# FPGA_DDR3_IO.net
KiCad netlist of a schematic drawn in Altium Designer
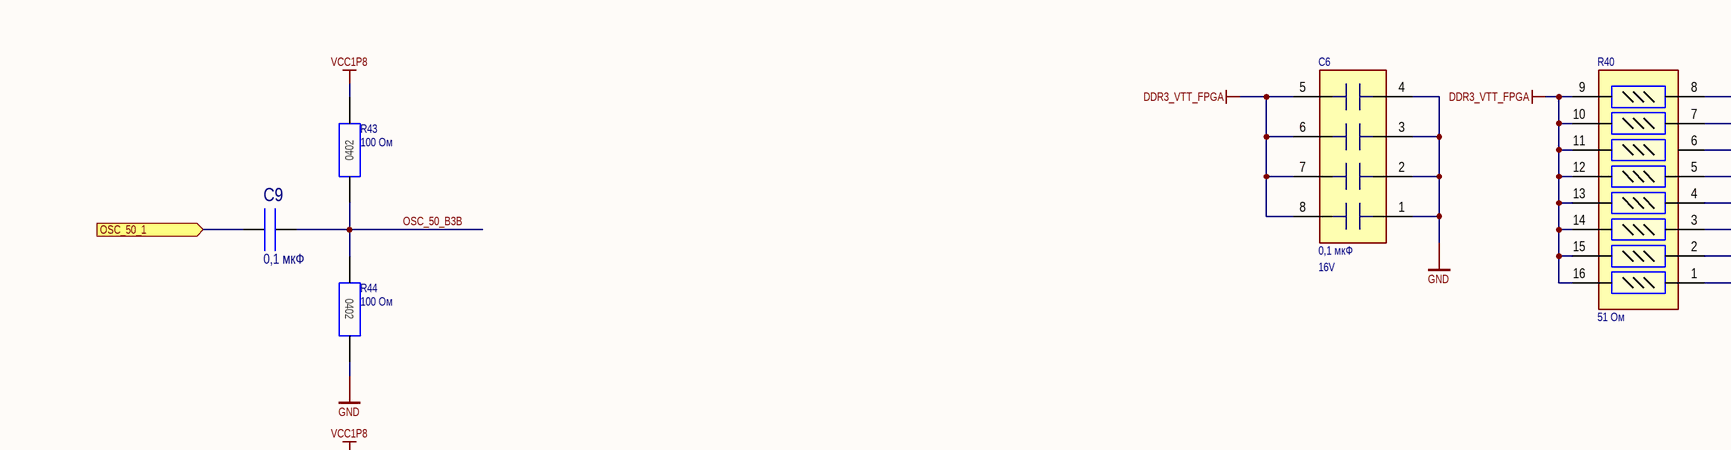
[diagram p0: FPGA_DDR3&IO.SchDoc, top left]
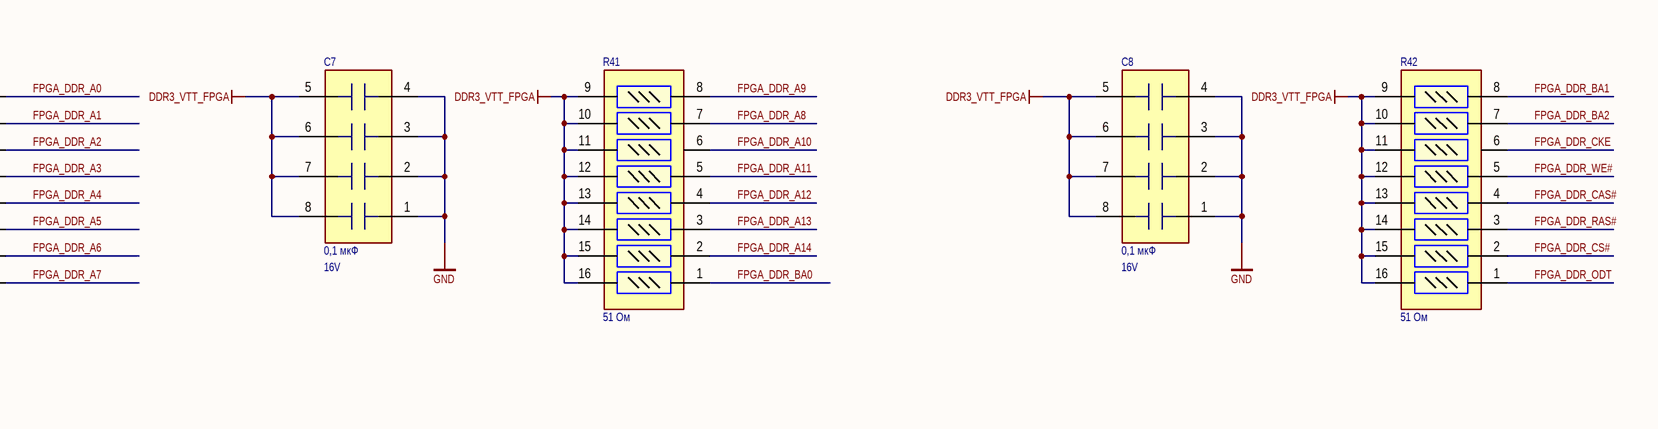
[diagram p1: FPGA_DDR3&IO.SchDoc, top right]
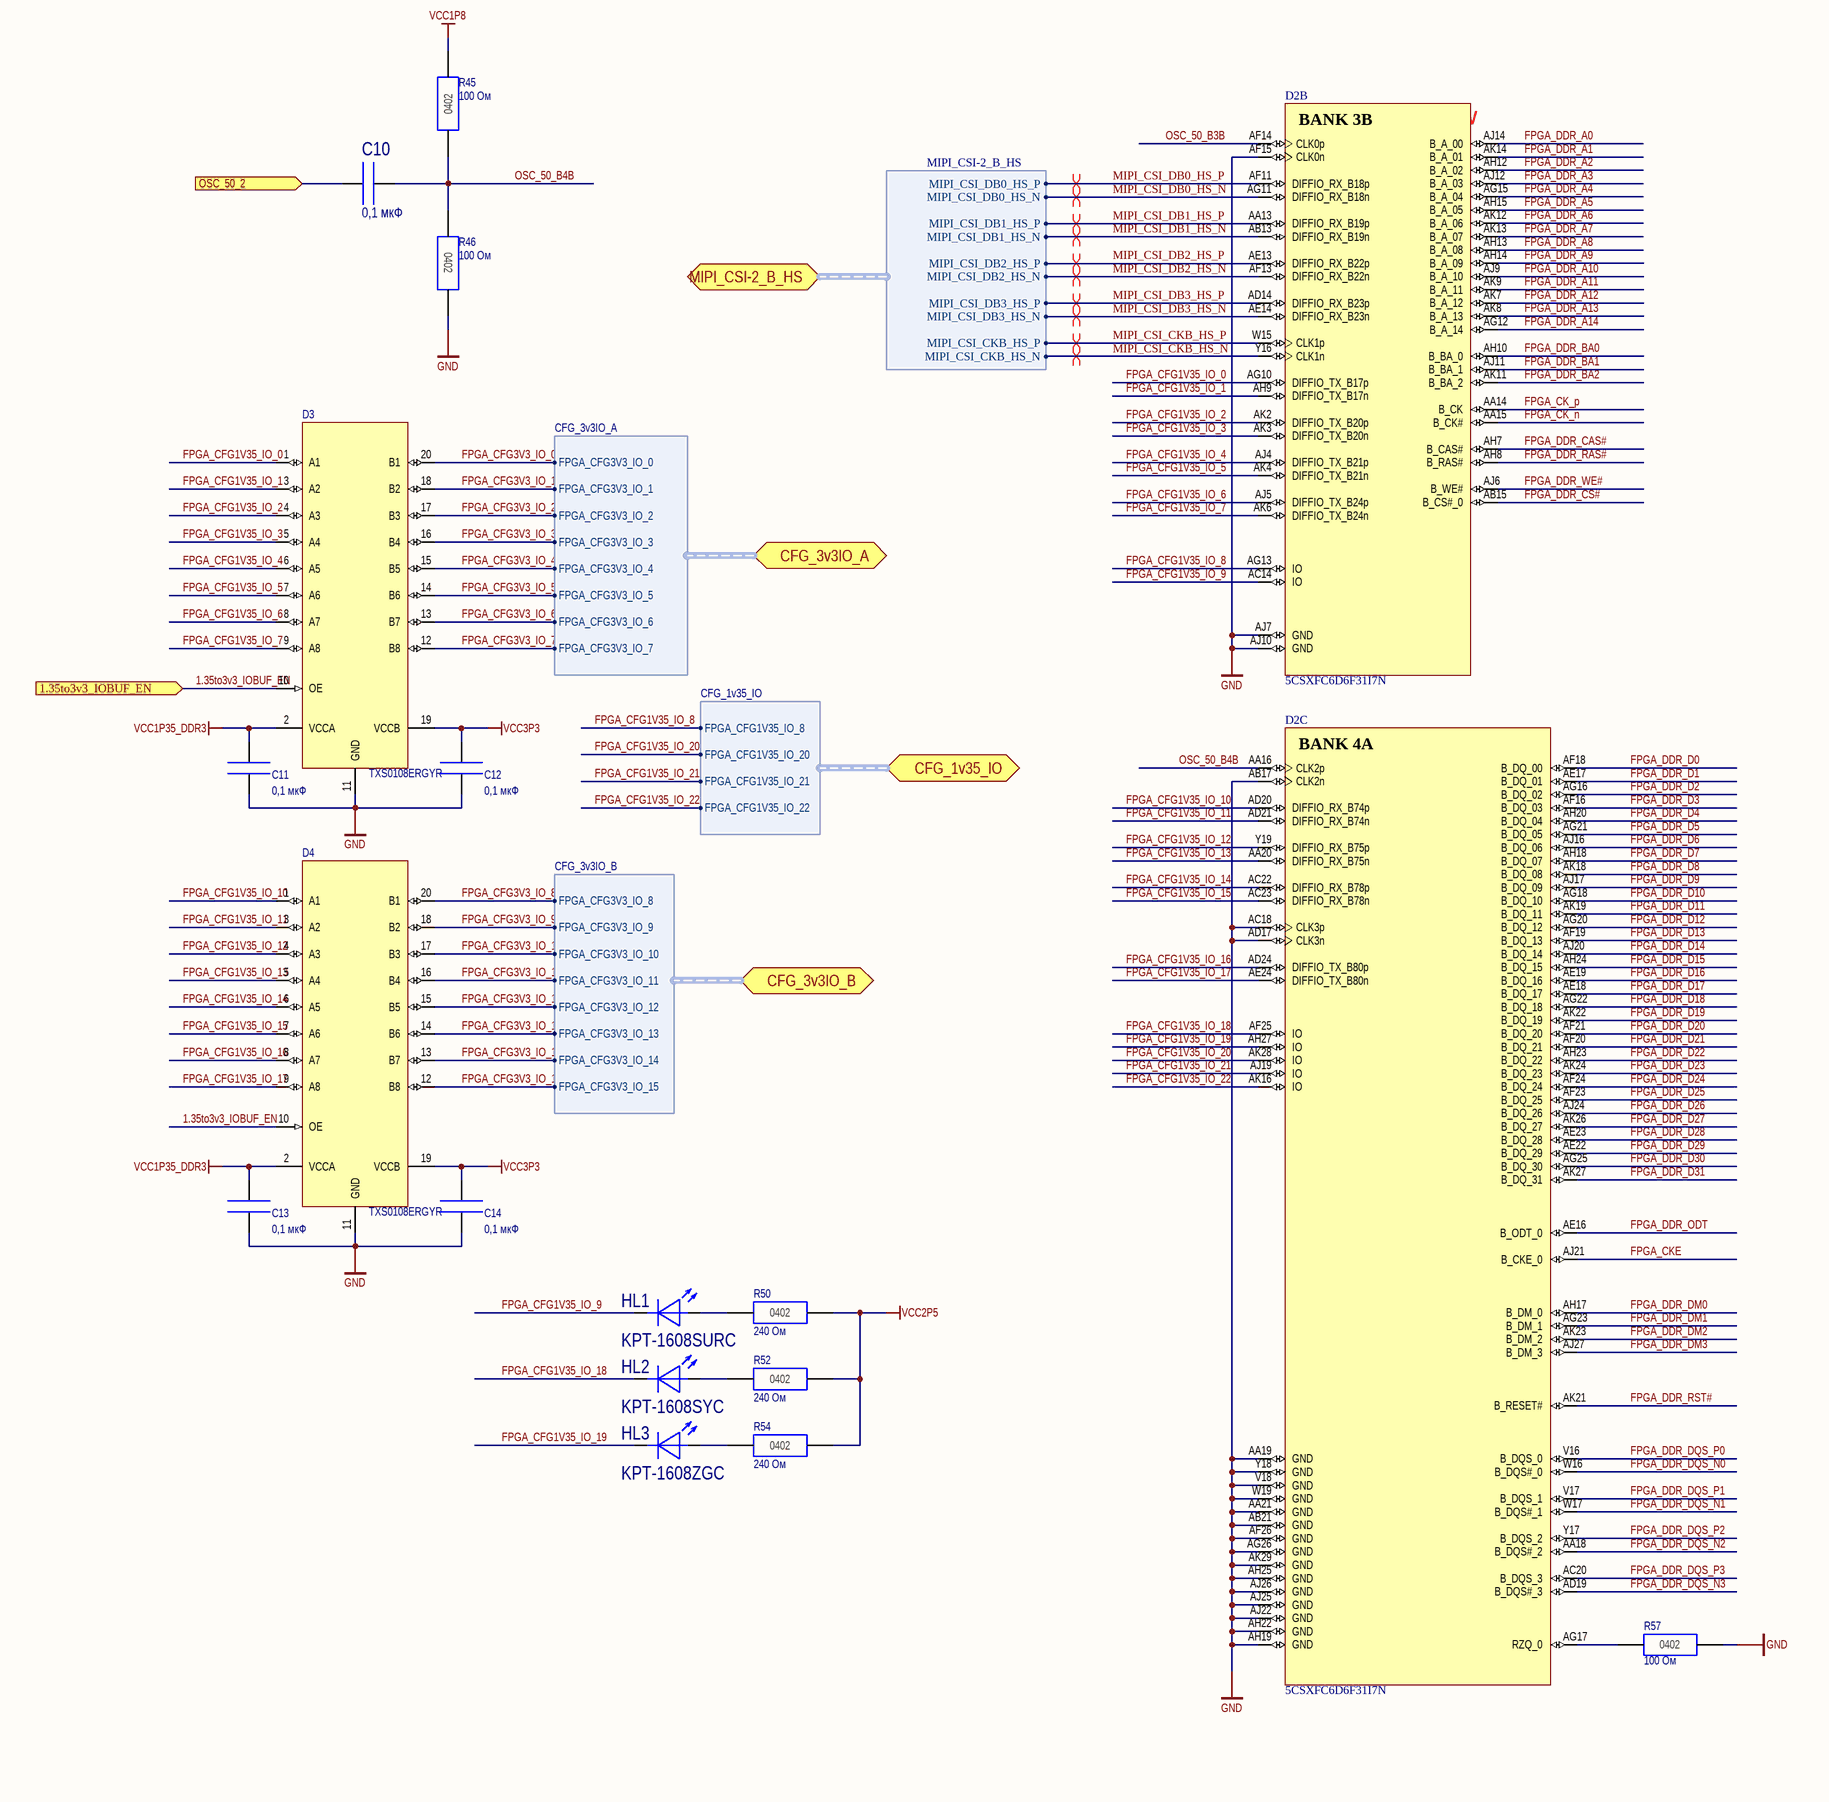
[diagram p2: FPGA_DDR3&IO.SchDoc, bottom left]
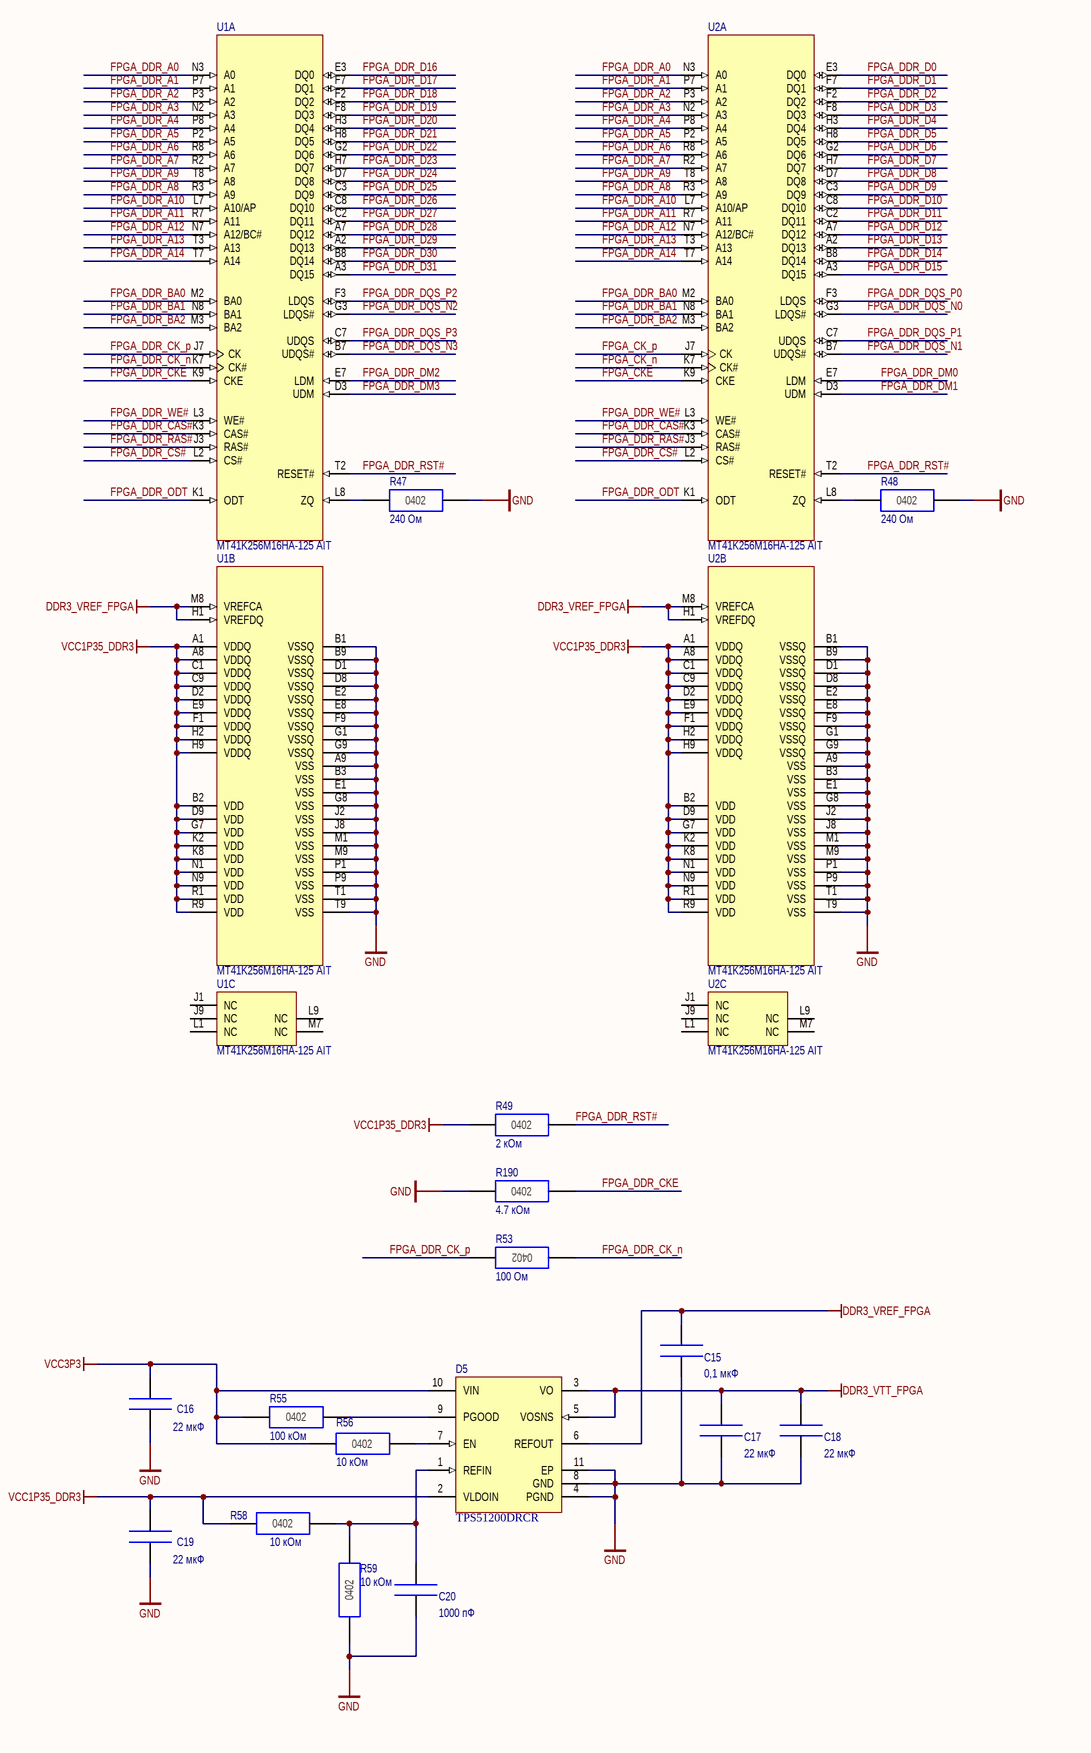
[diagram p3: FPGA_DDR3&IO.SchDoc, bottom right]

(export (version "E")
  (design (tool "Eeschema 10.0.6"))
  (components
    (comp (ref "C6")
      (value "0,1 мкФ")
      (footprint "CAF-80P319X159-8N")
      (description "Чип конденсатор керамический")
      (fields (field (name "V") "16V") (field (name "Comment") "W3A4YC104KAT2A"))
      (libsource (lib "SD_IC") (part "W3A4YC104KAT2A"))
    )
    (comp (ref "C7")
      (value "0,1 мкФ")
      (footprint "CAF-80P319X159-8N")
      (description "Чип конденсатор керамический")
      (fields (field (name "V") "16V") (field (name "Comment") "W3A4YC104KAT2A"))
      (libsource (lib "SD_IC") (part "W3A4YC104KAT2A"))
    )
    (comp (ref "C8")
      (value "0,1 мкФ")
      (footprint "CAF-80P319X159-8N")
      (description "Чип конденсатор керамический")
      (fields (field (name "V") "16V") (field (name "Comment") "W3A4YC104KAT2A"))
      (libsource (lib "SD_IC") (part "W3A4YC104KAT2A"))
    )
    (comp (ref "C9")
      (value "0,1 мкФ")
      (footprint "CC0402(1005)")
      (description "Чип конденсатор керамический")
      (fields (field (name "Comment") "CC0402-X7R-0,1 мкФ-20%-10В"))
      (libsource (lib "Чип конденсаторы") (part "CC0402-X7R-#-20%-10В"))
    )
    (comp (ref "C10")
      (value "0,1 мкФ")
      (footprint "CC0402(1005)")
      (description "Чип конденсатор керамический")
      (fields (field (name "Comment") "CC0402-X7R-0,1 мкФ-20%-10В"))
      (libsource (lib "Чип конденсаторы") (part "CC0402-X7R-#-20%-10В"))
    )
    (comp (ref "C11")
      (value "0,1 мкФ")
      (footprint "CC0402(1005)")
      (description "Чип конденсатор керамический")
      (fields (field (name "Comment") "CC0402-X7R-0,1 мкФ-20%-10В"))
      (libsource (lib "Чип конденсаторы") (part "CC0402-X7R-#-20%-10В"))
    )
    (comp (ref "C12")
      (value "0,1 мкФ")
      (footprint "CC0402(1005)")
      (description "Чип конденсатор керамический")
      (fields (field (name "Comment") "CC0402-X7R-0,1 мкФ-20%-10В"))
      (libsource (lib "Чип конденсаторы") (part "CC0402-X7R-#-20%-10В"))
    )
    (comp (ref "C13")
      (value "0,1 мкФ")
      (footprint "CC0402(1005)")
      (description "Чип конденсатор керамический")
      (fields (field (name "Comment") "CC0402-X7R-0,1 мкФ-20%-10В"))
      (libsource (lib "Чип конденсаторы") (part "CC0402-X7R-#-20%-10В"))
    )
    (comp (ref "C14")
      (value "0,1 мкФ")
      (footprint "CC0402(1005)")
      (description "Чип конденсатор керамический")
      (fields (field (name "Comment") "CC0402-X7R-0,1 мкФ-20%-10В"))
      (libsource (lib "Чип конденсаторы") (part "CC0402-X7R-#-20%-10В"))
    )
    (comp (ref "C15")
      (value "0,1 мкФ")
      (footprint "CC0402(1005)")
      (description "Чип конденсатор керамический")
      (fields (field (name "Comment") "CC0402-X7R-0,1 мкФ-20%-10В"))
      (libsource (lib "Чип конденсаторы") (part "CC0402-X7R-#-20%-10В"))
    )
    (comp (ref "C16")
      (value "22 мкФ")
      (footprint "CC0402(1005)")
      (description "Чип конденсатор керамический")
      (fields (field (name "Comment") "CC0402-X5R-22 мкФ-20%-6.3В"))
      (libsource (lib "Чип конденсаторы") (part "CC0402-X7R-#-20%-10В"))
    )
    (comp (ref "C17")
      (value "22 мкФ")
      (footprint "CC0402(1005)")
      (description "Чип конденсатор керамический")
      (fields (field (name "Comment") "CC0402-X5R-22 мкФ-20%-6.3В"))
      (libsource (lib "Чип конденсаторы") (part "CC0402-X7R-#-20%-10В"))
    )
    (comp (ref "C18")
      (value "22 мкФ")
      (footprint "CC0402(1005)")
      (description "Чип конденсатор керамический")
      (fields (field (name "Comment") "CC0402-X5R-22 мкФ-20%-6.3В"))
      (libsource (lib "Чип конденсаторы") (part "CC0402-X7R-#-20%-10В"))
    )
    (comp (ref "C19")
      (value "22 мкФ")
      (footprint "CC0402(1005)")
      (description "Чип конденсатор керамический")
      (fields (field (name "Comment") "CC0402-X5R-22 мкФ-20%-6.3В"))
      (libsource (lib "Чип конденсаторы") (part "CC0402-X7R-#-20%-10В"))
    )
    (comp (ref "C20")
      (value "1000 пФ")
      (footprint "CC0402(1005)")
      (description "Чип конденсатор керамический")
      (fields (field (name "Comment") "CC0402-NP01000 пФ-1%-50В"))
      (libsource (lib "Чип конденсаторы") (part "CC0402-X7R-#-20%-10В"))
    )
    (comp (ref "D2")
      (value "5CSXFC6D6F31I7N")
      (footprint "ALTR-FBGA896_A-200")
      (fields (field (name "MANUFACTURER") "Altera"))
      (libsource (lib "Altera Cyclone V_sd") (part "5CSXFC6D6F31I7N"))
    )
    (comp (ref "D3")
      (value "TXS0108ERGYR")
      (footprint "QFN50P450X350X100_HS-21N")
      (fields
        (field (name "GENERIC PART NUMBER") "TXB0108")
        (field (name "MANUFACTURER") "Texas Instruments")
      )
      (libsource (lib "SD_IC") (part "TXS0108ERGYR"))
    )
    (comp (ref "D4")
      (value "TXS0108ERGYR")
      (footprint "QFN50P450X350X100_HS-21N")
      (fields
        (field (name "GENERIC PART NUMBER") "TXB0108")
        (field (name "MANUFACTURER") "Texas Instruments")
      )
      (libsource (lib "SD_IC") (part "TXS0108ERGYR"))
    )
    (comp (ref "D5")
      (value "TPS51200DRCR")
      (footprint "TI-DRC10-2400X1650TP_V")
      (fields (field (name "MANUFACTURER") "Texas Instruments"))
      (libsource (lib "SD_IC") (part "TPS51200DRCR"))
    )
    (comp (ref "HL1")
      (value "KPT-1608SURC")
      (footprint "LED0603_Red")
      (description "Светодиод красный SMD0603")
      (libsource (lib "Индикация") (part "KPT-1608SURC"))
    )
    (comp (ref "HL2")
      (value "KPT-1608SYC")
      (footprint "LED0603_Yellow")
      (description "Светодиод желтый SMD0603")
      (libsource (lib "Индикация") (part "KPT-1608SYC"))
    )
    (comp (ref "HL3")
      (value "KPT-1608ZGC")
      (footprint "LED0603_GREEN")
      (description "Светодиод зеленый SMD0603")
      (libsource (lib "Индикация") (part "KPT-1608ZGC"))
    )
    (comp (ref "R40")
      (value "51 Ом")
      (footprint "CAT16-J8")
      (description "Набор чип резисторов")
      (fields (field (name "Comment") "YC248-JR-07-51 Ом"))
      (libsource (lib "SD_IC") (part "YC248-JR-07-#"))
    )
    (comp (ref "R41")
      (value "51 Ом")
      (footprint "CAT16-J8")
      (description "Набор чип резисторов")
      (fields (field (name "Comment") "YC248-JR-07-51 Ом"))
      (libsource (lib "SD_IC") (part "YC248-JR-07-#"))
    )
    (comp (ref "R42")
      (value "51 Ом")
      (footprint "CAT16-J8")
      (description "Набор чип резисторов")
      (fields (field (name "Comment") "YC248-JR-07-51 Ом"))
      (libsource (lib "SD_IC") (part "YC248-JR-07-#"))
    )
    (comp (ref "R43")
      (value "100 Ом")
      (footprint "CR0402(1005)")
      (description "Чип резистор")
      (fields (field (name "TOLERANCE") "5%") (field (name "Comment") "CR0402-100 Ом-±5%"))
      (libsource (lib "") (part "CR0402-#-±5%_3"))
    )
    (comp (ref "R44")
      (value "100 Ом")
      (footprint "CR0402(1005)")
      (description "Чип резистор")
      (fields (field (name "TOLERANCE") "5%") (field (name "Comment") "CR0402-100 Ом-±5%"))
      (libsource (lib "") (part "CR0402-#-±5%_2"))
    )
    (comp (ref "R45")
      (value "100 Ом")
      (footprint "CR0402(1005)")
      (description "Чип резистор")
      (fields (field (name "TOLERANCE") "5%") (field (name "Comment") "CR0402-100 Ом-±5%"))
      (libsource (lib "") (part "CR0402-#-±5%_3"))
    )
    (comp (ref "R46")
      (value "100 Ом")
      (footprint "CR0402(1005)")
      (description "Чип резистор")
      (fields (field (name "TOLERANCE") "5%") (field (name "Comment") "CR0402-100 Ом-±5%"))
      (libsource (lib "") (part "CR0402-#-±5%_2"))
    )
    (comp (ref "R47")
      (value "240 Ом")
      (footprint "CR0402(1005)")
      (description "Чип резистор")
      (fields (field (name "TOLERANCE") "5%") (field (name "Comment") "CR0402-240 Ом-±5%"))
      (libsource (lib "") (part "CR0402-#-±5%_1"))
    )
    (comp (ref "R48")
      (value "240 Ом")
      (footprint "CR0402(1005)")
      (description "Чип резистор")
      (fields (field (name "TOLERANCE") "5%") (field (name "Comment") "CR0402-240 Ом-±5%"))
      (libsource (lib "") (part "CR0402-#-±5%_1"))
    )
    (comp (ref "R49")
      (value "2 кОм")
      (footprint "CR0402(1005)")
      (description "Чип резистор")
      (fields (field (name "TOLERANCE") "5%") (field (name "Comment") "CR0402-2 кОм-±5%"))
      (libsource (lib "") (part "CR0402-#-±5%_1"))
    )
    (comp (ref "R50")
      (value "240 Ом")
      (footprint "CR0402(1005)")
      (description "Чип резистор")
      (fields (field (name "TOLERANCE") "5%") (field (name "Comment") "CR0402-240 Ом-±5%"))
      (libsource (lib "") (part "CR0402-#-±5%_1"))
    )
    (comp (ref "R52")
      (value "240 Ом")
      (footprint "CR0402(1005)")
      (description "Чип резистор")
      (fields (field (name "TOLERANCE") "5%") (field (name "Comment") "CR0402-240 Ом-±5%"))
      (libsource (lib "") (part "CR0402-#-±5%_1"))
    )
    (comp (ref "R53")
      (value "100 Ом")
      (footprint "CR0402(1005)")
      (description "Чип резистор")
      (fields (field (name "TOLERANCE") "5%") (field (name "Comment") "CR0402-100 Ом-±5%"))
      (libsource (lib "Резисторы") (part "CR0402-#-±5%"))
    )
    (comp (ref "R54")
      (value "240 Ом")
      (footprint "CR0402(1005)")
      (description "Чип резистор")
      (fields (field (name "TOLERANCE") "5%") (field (name "Comment") "CR0402-240 Ом-±5%"))
      (libsource (lib "") (part "CR0402-#-±5%_1"))
    )
    (comp (ref "R55")
      (value "100 кОм")
      (footprint "CR0402(1005)")
      (description "Чип резистор")
      (fields (field (name "TOLERANCE") "5%") (field (name "Comment") "CR0402-100 кОм-±5%"))
      (libsource (lib "") (part "CR0402-#-±5%_1"))
    )
    (comp (ref "R56")
      (value "10 кОм")
      (footprint "CR0402(1005)")
      (description "Чип резистор")
      (fields (field (name "TOLERANCE") "5%") (field (name "Comment") "CR0402-10 кОм-±5%"))
      (libsource (lib "") (part "CR0402-#-±5%_1"))
    )
    (comp (ref "R57")
      (value "100 Ом")
      (footprint "CR0402(1005)")
      (description "Чип резистор")
      (fields (field (name "TOLERANCE") "5%") (field (name "Comment") "CR0402-100 Ом-±5%"))
      (libsource (lib "") (part "CR0402-#-±5%_1"))
    )
    (comp (ref "R58")
      (value "10 кОм")
      (footprint "CR0402(1005)")
      (description "Чип резистор")
      (fields (field (name "TOLERANCE") "5%") (field (name "Comment") "CR0402-10 кОм-±5%"))
      (libsource (lib "") (part "CR0402-#-±5%_1"))
    )
    (comp (ref "R59")
      (value "10 кОм")
      (footprint "CR0402(1005)")
      (description "Чип резистор")
      (fields (field (name "TOLERANCE") "5%") (field (name "Comment") "CR0402-10 кОм-±5%"))
      (libsource (lib "") (part "CR0402-#-±5%_3"))
    )
    (comp (ref "R190")
      (value "4.7 кОм")
      (footprint "CR0402(1005)")
      (description "Чип резистор")
      (fields (field (name "TOLERANCE") "5%") (field (name "Comment") "CR0402-4.7 кОм-±5%"))
      (libsource (lib "") (part "CR0402-#-±5%_1"))
    )
    (comp (ref "U1")
      (value "MT41K256M16HA-125 AIT")
      (footprint "MICT-HA-96")
      (description "4Gb DDR3-1600 SDRAM, 256Mb x 16, 1.25ns, 1.35V, -40 to 95 degC, 96-Ball FBGA, Pb-Free")
      (fields (field (name "VOLTAGE") "1.35V ") (field (name "MANUFACTURER") "Micron"))
      (libsource (lib "SD_IC") (part "MT41K256M16HA-125 AIT"))
    )
    (comp (ref "U2")
      (value "MT41K256M16HA-125 AIT")
      (footprint "MICT-HA-96")
      (description "4Gb DDR3-1600 SDRAM, 256Mb x 16, 1.25ns, 1.35V, -40 to 95 degC, 96-Ball FBGA, Pb-Free")
      (fields (field (name "VOLTAGE") "1.35V ") (field (name "MANUFACTURER") "Micron"))
      (libsource (lib "SD_IC") (part "MT41K256M16HA-125 AIT"))
    )
  )
  (nets
    (net (code "5") (name "/1.35to3v3_IOBUF_EN") (class "Default")
      (node (ref "D3") (pin "10") (pinfunction "OE_10") (pintype "input"))
      (node (ref "D4") (pin "10") (pinfunction "OE_10") (pintype "input"))
    )
    (net (code "6") (name "/FPGA_CFG1V35_IO_0") (class "Default")
      (node (ref "D2") (pin "AG10") (pinfunction "DIFFIO_TX_B17p_AG10") (pintype "bidirectional"))
      (node (ref "D3") (pin "1") (pinfunction "A1_1") (pintype "bidirectional"))
    )
    (net (code "7") (name "/FPGA_CFG1V35_IO_1") (class "Default")
      (node (ref "D2") (pin "AH9") (pinfunction "DIFFIO_TX_B17n_AH9") (pintype "bidirectional"))
      (node (ref "D3") (pin "3") (pinfunction "A2_3") (pintype "bidirectional"))
    )
    (net (code "8") (name "/FPGA_CFG1V35_IO_2") (class "Default")
      (node (ref "D2") (pin "AK2") (pinfunction "DIFFIO_TX_B20p_AK2") (pintype "bidirectional"))
      (node (ref "D3") (pin "4") (pinfunction "A3_4") (pintype "bidirectional"))
    )
    (net (code "9") (name "/FPGA_CFG1V35_IO_3") (class "Default")
      (node (ref "D2") (pin "AK3") (pinfunction "DIFFIO_TX_B20n_AK3") (pintype "bidirectional"))
      (node (ref "D3") (pin "5") (pinfunction "A4_5") (pintype "bidirectional"))
    )
    (net (code "10") (name "/FPGA_CFG1V35_IO_4") (class "Default")
      (node (ref "D2") (pin "AJ4") (pinfunction "DIFFIO_TX_B21p_AJ4") (pintype "bidirectional"))
      (node (ref "D3") (pin "6") (pinfunction "A5_6") (pintype "bidirectional"))
    )
    (net (code "11") (name "/FPGA_CFG1V35_IO_5") (class "Default")
      (node (ref "D2") (pin "AK4") (pinfunction "DIFFIO_TX_B21n_AK4") (pintype "bidirectional"))
      (node (ref "D3") (pin "7") (pinfunction "A6_7") (pintype "bidirectional"))
    )
    (net (code "12") (name "/FPGA_CFG1V35_IO_6") (class "Default")
      (node (ref "D2") (pin "AJ5") (pinfunction "DIFFIO_TX_B24p_AJ5") (pintype "bidirectional"))
      (node (ref "D3") (pin "8") (pinfunction "A7_8") (pintype "bidirectional"))
    )
    (net (code "13") (name "/FPGA_CFG1V35_IO_7") (class "Default")
      (node (ref "D2") (pin "AK6") (pinfunction "DIFFIO_TX_B24n_AK6") (pintype "bidirectional"))
      (node (ref "D3") (pin "9") (pinfunction "A8_9") (pintype "bidirectional"))
    )
    (net (code "14") (name "/FPGA_CFG1V35_IO_8") (class "Default")
      (node (ref "D2") (pin "AG13") (pinfunction "IO_AG13") (pintype "bidirectional"))
    )
    (net (code "15") (name "/FPGA_CFG1V35_IO_9") (class "Default")
      (node (ref "D2") (pin "AC14") (pinfunction "IO_AC14") (pintype "bidirectional"))
      (node (ref "HL1") (pin "2") (pinfunction "K_2") (pintype "passive"))
    )
    (net (code "16") (name "/FPGA_CFG1V35_IO_10") (class "Default")
      (node (ref "D2") (pin "AD20") (pinfunction "DIFFIO_RX_B74p_AD20") (pintype "bidirectional"))
      (node (ref "D4") (pin "1") (pinfunction "A1_1") (pintype "bidirectional"))
    )
    (net (code "17") (name "/FPGA_CFG1V35_IO_11") (class "Default")
      (node (ref "D2") (pin "AD21") (pinfunction "DIFFIO_RX_B74n_AD21") (pintype "bidirectional"))
      (node (ref "D4") (pin "3") (pinfunction "A2_3") (pintype "bidirectional"))
    )
    (net (code "18") (name "/FPGA_CFG1V35_IO_12") (class "Default")
      (node (ref "D2") (pin "Y19") (pinfunction "DIFFIO_RX_B75p_Y19") (pintype "bidirectional"))
      (node (ref "D4") (pin "4") (pinfunction "A3_4") (pintype "bidirectional"))
    )
    (net (code "19") (name "/FPGA_CFG1V35_IO_13") (class "Default")
      (node (ref "D2") (pin "AA20") (pinfunction "DIFFIO_RX_B75n_AA20") (pintype "bidirectional"))
      (node (ref "D4") (pin "5") (pinfunction "A4_5") (pintype "bidirectional"))
    )
    (net (code "20") (name "/FPGA_CFG1V35_IO_14") (class "Default")
      (node (ref "D2") (pin "AC22") (pinfunction "DIFFIO_RX_B78p_AC22") (pintype "bidirectional"))
      (node (ref "D4") (pin "6") (pinfunction "A5_6") (pintype "bidirectional"))
    )
    (net (code "21") (name "/FPGA_CFG1V35_IO_15") (class "Default")
      (node (ref "D2") (pin "AC23") (pinfunction "DIFFIO_RX_B78n_AC23") (pintype "bidirectional"))
      (node (ref "D4") (pin "7") (pinfunction "A6_7") (pintype "bidirectional"))
    )
    (net (code "22") (name "/FPGA_CFG1V35_IO_16") (class "Default")
      (node (ref "D2") (pin "AD24") (pinfunction "DIFFIO_TX_B80p_AD24") (pintype "bidirectional"))
      (node (ref "D4") (pin "8") (pinfunction "A7_8") (pintype "bidirectional"))
    )
    (net (code "23") (name "/FPGA_CFG1V35_IO_17") (class "Default")
      (node (ref "D2") (pin "AE24") (pinfunction "DIFFIO_TX_B80n_AE24") (pintype "bidirectional"))
      (node (ref "D4") (pin "9") (pinfunction "A8_9") (pintype "bidirectional"))
    )
    (net (code "24") (name "/FPGA_CFG1V35_IO_18") (class "Default")
      (node (ref "D2") (pin "AF25") (pinfunction "IO_AF25") (pintype "bidirectional"))
      (node (ref "HL2") (pin "2") (pinfunction "K_2") (pintype "passive"))
    )
    (net (code "25") (name "/FPGA_CFG1V35_IO_19") (class "Default")
      (node (ref "D2") (pin "AH27") (pinfunction "IO_AH27") (pintype "bidirectional"))
      (node (ref "HL3") (pin "2") (pinfunction "K_2") (pintype "passive"))
    )
    (net (code "26") (name "/FPGA_CFG1V35_IO_20") (class "Default")
      (node (ref "D2") (pin "AK28") (pinfunction "IO_AK28") (pintype "bidirectional"))
    )
    (net (code "27") (name "/FPGA_CFG1V35_IO_21") (class "Default")
      (node (ref "D2") (pin "AJ19") (pinfunction "IO_AJ19") (pintype "bidirectional"))
    )
    (net (code "28") (name "/FPGA_CFG1V35_IO_22") (class "Default")
      (node (ref "D2") (pin "AK16") (pinfunction "IO_AK16") (pintype "bidirectional"))
    )
    (net (code "29") (name "/FPGA_CFG3V3_IO_0") (class "Default")
      (node (ref "D3") (pin "20") (pinfunction "B1_20") (pintype "bidirectional"))
    )
    (net (code "30") (name "/FPGA_CFG3V3_IO_1") (class "Default")
      (node (ref "D3") (pin "18") (pinfunction "B2_18") (pintype "bidirectional"))
    )
    (net (code "31") (name "/FPGA_CFG3V3_IO_2") (class "Default")
      (node (ref "D3") (pin "17") (pinfunction "B3_17") (pintype "bidirectional"))
    )
    (net (code "32") (name "/FPGA_CFG3V3_IO_3") (class "Default")
      (node (ref "D3") (pin "16") (pinfunction "B4_16") (pintype "bidirectional"))
    )
    (net (code "33") (name "/FPGA_CFG3V3_IO_4") (class "Default")
      (node (ref "D3") (pin "15") (pinfunction "B5_15") (pintype "bidirectional"))
    )
    (net (code "34") (name "/FPGA_CFG3V3_IO_5") (class "Default")
      (node (ref "D3") (pin "14") (pinfunction "B6_14") (pintype "bidirectional"))
    )
    (net (code "35") (name "/FPGA_CFG3V3_IO_6") (class "Default")
      (node (ref "D3") (pin "13") (pinfunction "B7_13") (pintype "bidirectional"))
    )
    (net (code "36") (name "/FPGA_CFG3V3_IO_7") (class "Default")
      (node (ref "D3") (pin "12") (pinfunction "B8_12") (pintype "bidirectional"))
    )
    (net (code "37") (name "/FPGA_CFG3V3_IO_8") (class "Default")
      (node (ref "D4") (pin "20") (pinfunction "B1_20") (pintype "bidirectional"))
    )
    (net (code "38") (name "/FPGA_CFG3V3_IO_9") (class "Default")
      (node (ref "D4") (pin "18") (pinfunction "B2_18") (pintype "bidirectional"))
    )
    (net (code "39") (name "/FPGA_CFG3V3_IO_10") (class "Default")
      (node (ref "D4") (pin "17") (pinfunction "B3_17") (pintype "bidirectional"))
    )
    (net (code "40") (name "/FPGA_CFG3V3_IO_11") (class "Default")
      (node (ref "D4") (pin "16") (pinfunction "B4_16") (pintype "bidirectional"))
    )
    (net (code "41") (name "/FPGA_CFG3V3_IO_12") (class "Default")
      (node (ref "D4") (pin "15") (pinfunction "B5_15") (pintype "bidirectional"))
    )
    (net (code "42") (name "/FPGA_CFG3V3_IO_13") (class "Default")
      (node (ref "D4") (pin "14") (pinfunction "B6_14") (pintype "bidirectional"))
    )
    (net (code "43") (name "/FPGA_CFG3V3_IO_14") (class "Default")
      (node (ref "D4") (pin "13") (pinfunction "B7_13") (pintype "bidirectional"))
    )
    (net (code "44") (name "/FPGA_CFG3V3_IO_15") (class "Default")
      (node (ref "D4") (pin "12") (pinfunction "B8_12") (pintype "bidirectional"))
    )
    (net (code "45") (name "/FPGA_CKE") (class "Default")
      (node (ref "D2") (pin "AJ21") (pinfunction "B_CKE_0_AJ21") (pintype "bidirectional"))
      (node (ref "U2") (pin "K9") (pinfunction "CKE_K9") (pintype "input"))
    )
    (net (code "46") (name "/FPGA_CK_n") (class "Default")
      (node (ref "D2") (pin "AA15") (pinfunction "B_CK#_AA15") (pintype "bidirectional"))
      (node (ref "U2") (pin "K7") (pinfunction "CK#_K7") (pintype "input"))
    )
    (net (code "47") (name "/FPGA_CK_p") (class "Default")
      (node (ref "D2") (pin "AA14") (pinfunction "B_CK_AA14") (pintype "bidirectional"))
      (node (ref "U2") (pin "J7") (pinfunction "CK_J7") (pintype "input"))
    )
    (net (code "48") (name "/FPGA_DDR_A0") (class "Default")
      (node (ref "D2") (pin "AJ14") (pinfunction "B_A_00_AJ14") (pintype "bidirectional"))
      (node (ref "R40") (pin "8") (pintype "passive"))
      (node (ref "U1") (pin "N3") (pinfunction "A0_N3") (pintype "input"))
      (node (ref "U2") (pin "N3") (pinfunction "A0_N3") (pintype "input"))
    )
    (net (code "49") (name "/FPGA_DDR_A1") (class "Default")
      (node (ref "D2") (pin "AK14") (pinfunction "B_A_01_AK14") (pintype "bidirectional"))
      (node (ref "R40") (pin "7") (pintype "passive"))
      (node (ref "U1") (pin "P7") (pinfunction "A1_P7") (pintype "input"))
      (node (ref "U2") (pin "P7") (pinfunction "A1_P7") (pintype "input"))
    )
    (net (code "50") (name "/FPGA_DDR_A2") (class "Default")
      (node (ref "D2") (pin "AH12") (pinfunction "B_A_02_AH12") (pintype "bidirectional"))
      (node (ref "R40") (pin "6") (pintype "passive"))
      (node (ref "U1") (pin "P3") (pinfunction "A2_P3") (pintype "input"))
      (node (ref "U2") (pin "P3") (pinfunction "A2_P3") (pintype "input"))
    )
    (net (code "51") (name "/FPGA_DDR_A3") (class "Default")
      (node (ref "D2") (pin "AJ12") (pinfunction "B_A_03_AJ12") (pintype "bidirectional"))
      (node (ref "R40") (pin "5") (pintype "passive"))
      (node (ref "U1") (pin "N2") (pinfunction "A3_N2") (pintype "input"))
      (node (ref "U2") (pin "N2") (pinfunction "A3_N2") (pintype "input"))
    )
    (net (code "52") (name "/FPGA_DDR_A4") (class "Default")
      (node (ref "D2") (pin "AG15") (pinfunction "B_A_04_AG15") (pintype "bidirectional"))
      (node (ref "R40") (pin "4") (pintype "passive"))
      (node (ref "U1") (pin "P8") (pinfunction "A4_P8") (pintype "input"))
      (node (ref "U2") (pin "P8") (pinfunction "A4_P8") (pintype "input"))
    )
    (net (code "53") (name "/FPGA_DDR_A5") (class "Default")
      (node (ref "D2") (pin "AH15") (pinfunction "B_A_05_AH15") (pintype "bidirectional"))
      (node (ref "R40") (pin "3") (pintype "passive"))
      (node (ref "U1") (pin "P2") (pinfunction "A5_P2") (pintype "input"))
      (node (ref "U2") (pin "P2") (pinfunction "A5_P2") (pintype "input"))
    )
    (net (code "54") (name "/FPGA_DDR_A6") (class "Default")
      (node (ref "D2") (pin "AK12") (pinfunction "B_A_06_AK12") (pintype "bidirectional"))
      (node (ref "R40") (pin "2") (pintype "passive"))
      (node (ref "U1") (pin "R8") (pinfunction "A6_R8") (pintype "input"))
      (node (ref "U2") (pin "R8") (pinfunction "A6_R8") (pintype "input"))
    )
    (net (code "55") (name "/FPGA_DDR_A7") (class "Default")
      (node (ref "D2") (pin "AK13") (pinfunction "B_A_07_AK13") (pintype "bidirectional"))
      (node (ref "R40") (pin "1") (pintype "passive"))
      (node (ref "U1") (pin "R2") (pinfunction "A7_R2") (pintype "input"))
      (node (ref "U2") (pin "R2") (pinfunction "A7_R2") (pintype "input"))
    )
    (net (code "56") (name "/FPGA_DDR_A8") (class "Default")
      (node (ref "D2") (pin "AH13") (pinfunction "B_A_08_AH13") (pintype "bidirectional"))
      (node (ref "R41") (pin "7") (pintype "passive"))
      (node (ref "U1") (pin "R3") (pinfunction "A9_R3") (pintype "input"))
      (node (ref "U2") (pin "R3") (pinfunction "A9_R3") (pintype "input"))
    )
    (net (code "57") (name "/FPGA_DDR_A9") (class "Default")
      (node (ref "D2") (pin "AH14") (pinfunction "B_A_09_AH14") (pintype "bidirectional"))
      (node (ref "R41") (pin "8") (pintype "passive"))
      (node (ref "U1") (pin "T8") (pinfunction "A8_T8") (pintype "input"))
      (node (ref "U2") (pin "T8") (pinfunction "A8_T8") (pintype "input"))
    )
    (net (code "58") (name "/FPGA_DDR_A10") (class "Default")
      (node (ref "D2") (pin "AJ9") (pinfunction "B_A_10_AJ9") (pintype "bidirectional"))
      (node (ref "R41") (pin "6") (pintype "passive"))
      (node (ref "U1") (pin "L7") (pinfunction "A10/AP_L7") (pintype "input"))
      (node (ref "U2") (pin "L7") (pinfunction "A10/AP_L7") (pintype "input"))
    )
    (net (code "59") (name "/FPGA_DDR_A11") (class "Default")
      (node (ref "D2") (pin "AK9") (pinfunction "B_A_11_AK9") (pintype "bidirectional"))
      (node (ref "R41") (pin "5") (pintype "passive"))
      (node (ref "U1") (pin "R7") (pinfunction "A11_R7") (pintype "input"))
      (node (ref "U2") (pin "R7") (pinfunction "A11_R7") (pintype "input"))
    )
    (net (code "60") (name "/FPGA_DDR_A12") (class "Default")
      (node (ref "D2") (pin "AK7") (pinfunction "B_A_12_AK7") (pintype "bidirectional"))
      (node (ref "R41") (pin "4") (pintype "passive"))
      (node (ref "U1") (pin "N7") (pinfunction "A12/BC#_N7") (pintype "input"))
      (node (ref "U2") (pin "N7") (pinfunction "A12/BC#_N7") (pintype "input"))
    )
    (net (code "61") (name "/FPGA_DDR_A13") (class "Default")
      (node (ref "D2") (pin "AK8") (pinfunction "B_A_13_AK8") (pintype "bidirectional"))
      (node (ref "R41") (pin "3") (pintype "passive"))
      (node (ref "U1") (pin "T3") (pinfunction "A13_T3") (pintype "input"))
      (node (ref "U2") (pin "T3") (pinfunction "A13_T3") (pintype "input"))
    )
    (net (code "62") (name "/FPGA_DDR_A14") (class "Default")
      (node (ref "D2") (pin "AG12") (pinfunction "B_A_14_AG12") (pintype "bidirectional"))
      (node (ref "R41") (pin "2") (pintype "passive"))
      (node (ref "U1") (pin "T7") (pinfunction "A14_T7") (pintype "input"))
      (node (ref "U2") (pin "T7") (pinfunction "A14_T7") (pintype "input"))
    )
    (net (code "63") (name "/FPGA_DDR_BA0") (class "Default")
      (node (ref "D2") (pin "AH10") (pinfunction "B_BA_0_AH10") (pintype "bidirectional"))
      (node (ref "R41") (pin "1") (pintype "passive"))
      (node (ref "U1") (pin "M2") (pinfunction "BA0_M2") (pintype "input"))
      (node (ref "U2") (pin "M2") (pinfunction "BA0_M2") (pintype "input"))
    )
    (net (code "64") (name "/FPGA_DDR_BA1") (class "Default")
      (node (ref "D2") (pin "AJ11") (pinfunction "B_BA_1_AJ11") (pintype "bidirectional"))
      (node (ref "R42") (pin "8") (pintype "passive"))
      (node (ref "U1") (pin "N8") (pinfunction "BA1_N8") (pintype "input"))
      (node (ref "U2") (pin "N8") (pinfunction "BA1_N8") (pintype "input"))
    )
    (net (code "65") (name "/FPGA_DDR_BA2") (class "Default")
      (node (ref "D2") (pin "AK11") (pinfunction "B_BA_2_AK11") (pintype "bidirectional"))
      (node (ref "R42") (pin "7") (pintype "passive"))
      (node (ref "U1") (pin "M3") (pinfunction "BA2_M3") (pintype "input"))
      (node (ref "U2") (pin "M3") (pinfunction "BA2_M3") (pintype "input"))
    )
    (net (code "66") (name "/FPGA_DDR_CAS#") (class "Default")
      (node (ref "D2") (pin "AH7") (pinfunction "B_CAS#_AH7") (pintype "bidirectional"))
      (node (ref "R42") (pin "4") (pintype "passive"))
      (node (ref "U1") (pin "K3") (pinfunction "CAS#_K3") (pintype "input"))
      (node (ref "U2") (pin "K3") (pinfunction "CAS#_K3") (pintype "input"))
    )
    (net (code "67") (name "/FPGA_DDR_CKE") (class "Default")
      (node (ref "R190") (pin "2") (pinfunction "-_2") (pintype "passive"))
      (node (ref "R42") (pin "6") (pintype "passive"))
      (node (ref "U1") (pin "K9") (pinfunction "CKE_K9") (pintype "input"))
    )
    (net (code "68") (name "/FPGA_DDR_CK_n") (class "Default")
      (node (ref "R53") (pin "1") (pinfunction "+_1") (pintype "passive"))
      (node (ref "U1") (pin "K7") (pinfunction "CK#_K7") (pintype "input"))
    )
    (net (code "69") (name "/FPGA_DDR_CK_p") (class "Default")
      (node (ref "R53") (pin "2") (pinfunction "-_2") (pintype "passive"))
      (node (ref "U1") (pin "J7") (pinfunction "CK_J7") (pintype "input"))
    )
    (net (code "70") (name "/FPGA_DDR_CS#") (class "Default")
      (node (ref "D2") (pin "AB15") (pinfunction "B_CS#_0_AB15") (pintype "bidirectional"))
      (node (ref "R42") (pin "2") (pintype "passive"))
      (node (ref "U1") (pin "L2") (pinfunction "CS#_L2") (pintype "input"))
      (node (ref "U2") (pin "L2") (pinfunction "CS#_L2") (pintype "input"))
    )
    (net (code "71") (name "/FPGA_DDR_D0") (class "Default")
      (node (ref "D2") (pin "AF18") (pinfunction "B_DQ_00_AF18") (pintype "bidirectional"))
      (node (ref "U2") (pin "E3") (pinfunction "DQ0_E3") (pintype "bidirectional"))
    )
    (net (code "72") (name "/FPGA_DDR_D1") (class "Default")
      (node (ref "D2") (pin "AE17") (pinfunction "B_DQ_01_AE17") (pintype "bidirectional"))
      (node (ref "U2") (pin "F7") (pinfunction "DQ1_F7") (pintype "bidirectional"))
    )
    (net (code "73") (name "/FPGA_DDR_D2") (class "Default")
      (node (ref "D2") (pin "AG16") (pinfunction "B_DQ_02_AG16") (pintype "bidirectional"))
      (node (ref "U2") (pin "F2") (pinfunction "DQ2_F2") (pintype "bidirectional"))
    )
    (net (code "74") (name "/FPGA_DDR_D3") (class "Default")
      (node (ref "D2") (pin "AF16") (pinfunction "B_DQ_03_AF16") (pintype "bidirectional"))
      (node (ref "U2") (pin "F8") (pinfunction "DQ3_F8") (pintype "bidirectional"))
    )
    (net (code "75") (name "/FPGA_DDR_D4") (class "Default")
      (node (ref "D2") (pin "AH20") (pinfunction "B_DQ_04_AH20") (pintype "bidirectional"))
      (node (ref "U2") (pin "H3") (pinfunction "DQ4_H3") (pintype "bidirectional"))
    )
    (net (code "76") (name "/FPGA_DDR_D5") (class "Default")
      (node (ref "D2") (pin "AG21") (pinfunction "B_DQ_05_AG21") (pintype "bidirectional"))
      (node (ref "U2") (pin "H8") (pinfunction "DQ5_H8") (pintype "bidirectional"))
    )
    (net (code "77") (name "/FPGA_DDR_D6") (class "Default")
      (node (ref "D2") (pin "AJ16") (pinfunction "B_DQ_06_AJ16") (pintype "bidirectional"))
      (node (ref "U2") (pin "G2") (pinfunction "DQ6_G2") (pintype "bidirectional"))
    )
    (net (code "78") (name "/FPGA_DDR_D7") (class "Default")
      (node (ref "D2") (pin "AH18") (pinfunction "B_DQ_07_AH18") (pintype "bidirectional"))
      (node (ref "U2") (pin "H7") (pinfunction "DQ7_H7") (pintype "bidirectional"))
    )
    (net (code "79") (name "/FPGA_DDR_D8") (class "Default")
      (node (ref "D2") (pin "AK18") (pinfunction "B_DQ_08_AK18") (pintype "bidirectional"))
      (node (ref "U2") (pin "D7") (pinfunction "DQ8_D7") (pintype "bidirectional"))
    )
    (net (code "80") (name "/FPGA_DDR_D9") (class "Default")
      (node (ref "D2") (pin "AJ17") (pinfunction "B_DQ_09_AJ17") (pintype "bidirectional"))
      (node (ref "U2") (pin "C3") (pinfunction "DQ9_C3") (pintype "bidirectional"))
    )
    (net (code "81") (name "/FPGA_DDR_D10") (class "Default")
      (node (ref "D2") (pin "AG18") (pinfunction "B_DQ_10_AG18") (pintype "bidirectional"))
      (node (ref "U2") (pin "C8") (pinfunction "DQ10_C8") (pintype "bidirectional"))
    )
    (net (code "82") (name "/FPGA_DDR_D11") (class "Default")
      (node (ref "D2") (pin "AK19") (pinfunction "B_DQ_11_AK19") (pintype "bidirectional"))
      (node (ref "U2") (pin "C2") (pinfunction "DQ11_C2") (pintype "bidirectional"))
    )
    (net (code "83") (name "/FPGA_DDR_D12") (class "Default")
      (node (ref "D2") (pin "AG20") (pinfunction "B_DQ_12_AG20") (pintype "bidirectional"))
      (node (ref "U2") (pin "A7") (pinfunction "DQ12_A7") (pintype "bidirectional"))
    )
    (net (code "84") (name "/FPGA_DDR_D13") (class "Default")
      (node (ref "D2") (pin "AF19") (pinfunction "B_DQ_13_AF19") (pintype "bidirectional"))
      (node (ref "U2") (pin "A2") (pinfunction "DQ13_A2") (pintype "bidirectional"))
    )
    (net (code "85") (name "/FPGA_DDR_D14") (class "Default")
      (node (ref "D2") (pin "AJ20") (pinfunction "B_DQ_14_AJ20") (pintype "bidirectional"))
      (node (ref "U2") (pin "B8") (pinfunction "DQ14_B8") (pintype "bidirectional"))
    )
    (net (code "86") (name "/FPGA_DDR_D15") (class "Default")
      (node (ref "D2") (pin "AH24") (pinfunction "B_DQ_15_AH24") (pintype "bidirectional"))
      (node (ref "U2") (pin "A3") (pinfunction "DQ15_A3") (pintype "bidirectional"))
    )
    (net (code "87") (name "/FPGA_DDR_D16") (class "Default")
      (node (ref "D2") (pin "AE19") (pinfunction "B_DQ_16_AE19") (pintype "bidirectional"))
      (node (ref "U1") (pin "E3") (pinfunction "DQ0_E3") (pintype "bidirectional"))
    )
    (net (code "88") (name "/FPGA_DDR_D17") (class "Default")
      (node (ref "D2") (pin "AE18") (pinfunction "B_DQ_17_AE18") (pintype "bidirectional"))
      (node (ref "U1") (pin "F7") (pinfunction "DQ1_F7") (pintype "bidirectional"))
    )
    (net (code "89") (name "/FPGA_DDR_D18") (class "Default")
      (node (ref "D2") (pin "AG22") (pinfunction "B_DQ_18_AG22") (pintype "bidirectional"))
      (node (ref "U1") (pin "F2") (pinfunction "DQ2_F2") (pintype "bidirectional"))
    )
    (net (code "90") (name "/FPGA_DDR_D19") (class "Default")
      (node (ref "D2") (pin "AK22") (pinfunction "B_DQ_19_AK22") (pintype "bidirectional"))
      (node (ref "U1") (pin "F8") (pinfunction "DQ3_F8") (pintype "bidirectional"))
    )
    (net (code "91") (name "/FPGA_DDR_D20") (class "Default")
      (node (ref "D2") (pin "AF21") (pinfunction "B_DQ_20_AF21") (pintype "bidirectional"))
      (node (ref "U1") (pin "H3") (pinfunction "DQ4_H3") (pintype "bidirectional"))
    )
    (net (code "92") (name "/FPGA_DDR_D21") (class "Default")
      (node (ref "D2") (pin "AF20") (pinfunction "B_DQ_21_AF20") (pintype "bidirectional"))
      (node (ref "U1") (pin "H8") (pinfunction "DQ5_H8") (pintype "bidirectional"))
    )
    (net (code "93") (name "/FPGA_DDR_D22") (class "Default")
      (node (ref "D2") (pin "AH23") (pinfunction "B_DQ_22_AH23") (pintype "bidirectional"))
      (node (ref "U1") (pin "G2") (pinfunction "DQ6_G2") (pintype "bidirectional"))
    )
    (net (code "94") (name "/FPGA_DDR_D23") (class "Default")
      (node (ref "D2") (pin "AK24") (pinfunction "B_DQ_23_AK24") (pintype "bidirectional"))
      (node (ref "U1") (pin "H7") (pinfunction "DQ7_H7") (pintype "bidirectional"))
    )
    (net (code "95") (name "/FPGA_DDR_D24") (class "Default")
      (node (ref "D2") (pin "AF24") (pinfunction "B_DQ_24_AF24") (pintype "bidirectional"))
      (node (ref "U1") (pin "D7") (pinfunction "DQ8_D7") (pintype "bidirectional"))
    )
    (net (code "96") (name "/FPGA_DDR_D25") (class "Default")
      (node (ref "D2") (pin "AF23") (pinfunction "B_DQ_25_AF23") (pintype "bidirectional"))
      (node (ref "U1") (pin "C3") (pinfunction "DQ9_C3") (pintype "bidirectional"))
    )
    (net (code "97") (name "/FPGA_DDR_D26") (class "Default")
      (node (ref "D2") (pin "AJ24") (pinfunction "B_DQ_26_AJ24") (pintype "bidirectional"))
      (node (ref "U1") (pin "C8") (pinfunction "DQ10_C8") (pintype "bidirectional"))
    )
    (net (code "98") (name "/FPGA_DDR_D27") (class "Default")
      (node (ref "D2") (pin "AK26") (pinfunction "B_DQ_27_AK26") (pintype "bidirectional"))
      (node (ref "U1") (pin "C2") (pinfunction "DQ11_C2") (pintype "bidirectional"))
    )
    (net (code "99") (name "/FPGA_DDR_D28") (class "Default")
      (node (ref "D2") (pin "AE23") (pinfunction "B_DQ_28_AE23") (pintype "bidirectional"))
      (node (ref "U1") (pin "A7") (pinfunction "DQ12_A7") (pintype "bidirectional"))
    )
    (net (code "100") (name "/FPGA_DDR_D29") (class "Default")
      (node (ref "D2") (pin "AE22") (pinfunction "B_DQ_29_AE22") (pintype "bidirectional"))
      (node (ref "U1") (pin "A2") (pinfunction "DQ13_A2") (pintype "bidirectional"))
    )
    (net (code "101") (name "/FPGA_DDR_D30") (class "Default")
      (node (ref "D2") (pin "AG25") (pinfunction "B_DQ_30_AG25") (pintype "bidirectional"))
      (node (ref "U1") (pin "B8") (pinfunction "DQ14_B8") (pintype "bidirectional"))
    )
    (net (code "102") (name "/FPGA_DDR_D31") (class "Default")
      (node (ref "D2") (pin "AK27") (pinfunction "B_DQ_31_AK27") (pintype "bidirectional"))
      (node (ref "U1") (pin "A3") (pinfunction "DQ15_A3") (pintype "bidirectional"))
    )
    (net (code "103") (name "/FPGA_DDR_DM0") (class "Default")
      (node (ref "D2") (pin "AH17") (pinfunction "B_DM_0_AH17") (pintype "bidirectional"))
      (node (ref "U2") (pin "E7") (pinfunction "LDM_E7") (pintype "input"))
    )
    (net (code "104") (name "/FPGA_DDR_DM1") (class "Default")
      (node (ref "D2") (pin "AG23") (pinfunction "B_DM_1_AG23") (pintype "bidirectional"))
      (node (ref "U2") (pin "D3") (pinfunction "UDM_D3") (pintype "input"))
    )
    (net (code "105") (name "/FPGA_DDR_DM2") (class "Default")
      (node (ref "D2") (pin "AK23") (pinfunction "B_DM_2_AK23") (pintype "bidirectional"))
      (node (ref "U1") (pin "E7") (pinfunction "LDM_E7") (pintype "input"))
    )
    (net (code "106") (name "/FPGA_DDR_DM3") (class "Default")
      (node (ref "D2") (pin "AJ27") (pinfunction "B_DM_3_AJ27") (pintype "bidirectional"))
      (node (ref "U1") (pin "D3") (pinfunction "UDM_D3") (pintype "input"))
    )
    (net (code "107") (name "/FPGA_DDR_DQS_N0") (class "Default")
      (node (ref "D2") (pin "W16") (pinfunction "B_DQS#_0_W16") (pintype "bidirectional"))
      (node (ref "U2") (pin "G3") (pinfunction "LDQS#_G3") (pintype "bidirectional"))
    )
    (net (code "108") (name "/FPGA_DDR_DQS_N1") (class "Default")
      (node (ref "D2") (pin "W17") (pinfunction "B_DQS#_1_W17") (pintype "bidirectional"))
      (node (ref "U2") (pin "B7") (pinfunction "UDQS#_B7") (pintype "bidirectional"))
    )
    (net (code "109") (name "/FPGA_DDR_DQS_N2") (class "Default")
      (node (ref "D2") (pin "AA18") (pinfunction "B_DQS#_2_AA18") (pintype "bidirectional"))
      (node (ref "U1") (pin "G3") (pinfunction "LDQS#_G3") (pintype "bidirectional"))
    )
    (net (code "110") (name "/FPGA_DDR_DQS_N3") (class "Default")
      (node (ref "D2") (pin "AD19") (pinfunction "B_DQS#_3_AD19") (pintype "bidirectional"))
      (node (ref "U1") (pin "B7") (pinfunction "UDQS#_B7") (pintype "bidirectional"))
    )
    (net (code "111") (name "/FPGA_DDR_DQS_P0") (class "Default")
      (node (ref "D2") (pin "V16") (pinfunction "B_DQS_0_V16") (pintype "bidirectional"))
      (node (ref "U2") (pin "F3") (pinfunction "LDQS_F3") (pintype "bidirectional"))
    )
    (net (code "112") (name "/FPGA_DDR_DQS_P1") (class "Default")
      (node (ref "D2") (pin "V17") (pinfunction "B_DQS_1_V17") (pintype "bidirectional"))
      (node (ref "U2") (pin "C7") (pinfunction "UDQS_C7") (pintype "bidirectional"))
    )
    (net (code "113") (name "/FPGA_DDR_DQS_P2") (class "Default")
      (node (ref "D2") (pin "Y17") (pinfunction "B_DQS_2_Y17") (pintype "bidirectional"))
      (node (ref "U1") (pin "F3") (pinfunction "LDQS_F3") (pintype "bidirectional"))
    )
    (net (code "114") (name "/FPGA_DDR_DQS_P3") (class "Default")
      (node (ref "D2") (pin "AC20") (pinfunction "B_DQS_3_AC20") (pintype "bidirectional"))
      (node (ref "U1") (pin "C7") (pinfunction "UDQS_C7") (pintype "bidirectional"))
    )
    (net (code "115") (name "/FPGA_DDR_ODT") (class "Default")
      (node (ref "D2") (pin "AE16") (pinfunction "B_ODT_0_AE16") (pintype "bidirectional"))
      (node (ref "R42") (pin "1") (pintype "passive"))
      (node (ref "U1") (pin "K1") (pinfunction "ODT_K1") (pintype "input"))
      (node (ref "U2") (pin "K1") (pinfunction "ODT_K1") (pintype "input"))
    )
    (net (code "116") (name "/FPGA_DDR_RAS#") (class "Default")
      (node (ref "D2") (pin "AH8") (pinfunction "B_RAS#_AH8") (pintype "bidirectional"))
      (node (ref "R42") (pin "3") (pintype "passive"))
      (node (ref "U1") (pin "J3") (pinfunction "RAS#_J3") (pintype "input"))
      (node (ref "U2") (pin "J3") (pinfunction "RAS#_J3") (pintype "input"))
    )
    (net (code "117") (name "/FPGA_DDR_RST#") (class "Default")
      (node (ref "D2") (pin "AK21") (pinfunction "B_RESET#_AK21") (pintype "bidirectional"))
      (node (ref "R49") (pin "2") (pinfunction "-_2") (pintype "passive"))
      (node (ref "U1") (pin "T2") (pinfunction "RESET#_T2") (pintype "input"))
      (node (ref "U2") (pin "T2") (pinfunction "RESET#_T2") (pintype "input"))
    )
    (net (code "118") (name "/FPGA_DDR_WE#") (class "Default")
      (node (ref "D2") (pin "AJ6") (pinfunction "B_WE#_AJ6") (pintype "bidirectional"))
      (node (ref "R42") (pin "5") (pintype "passive"))
      (node (ref "U1") (pin "L3") (pinfunction "WE#_L3") (pintype "input"))
      (node (ref "U2") (pin "L3") (pinfunction "WE#_L3") (pintype "input"))
    )
    (net (code "120") (name "/MIPI_CSI_CKB_HS_N") (class "Default")
      (node (ref "D2") (pin "Y16") (pinfunction "CLK1n_Y16") (pintype "bidirectional"))
    )
    (net (code "121") (name "/MIPI_CSI_CKB_HS_P") (class "Default")
      (node (ref "D2") (pin "W15") (pinfunction "CLK1p_W15") (pintype "bidirectional"))
    )
    (net (code "122") (name "/MIPI_CSI_DB0_HS_N") (class "Default")
      (node (ref "D2") (pin "AG11") (pinfunction "DIFFIO_RX_B18n_AG11") (pintype "bidirectional"))
    )
    (net (code "123") (name "/MIPI_CSI_DB0_HS_P") (class "Default")
      (node (ref "D2") (pin "AF11") (pinfunction "DIFFIO_RX_B18p_AF11") (pintype "bidirectional"))
    )
    (net (code "124") (name "/MIPI_CSI_DB1_HS_N") (class "Default")
      (node (ref "D2") (pin "AB13") (pinfunction "DIFFIO_RX_B19n_AB13") (pintype "bidirectional"))
    )
    (net (code "125") (name "/MIPI_CSI_DB1_HS_P") (class "Default")
      (node (ref "D2") (pin "AA13") (pinfunction "DIFFIO_RX_B19p_AA13") (pintype "bidirectional"))
    )
    (net (code "127") (name "/MIPI_CSI_DB2_HS_N") (class "Default")
      (node (ref "D2") (pin "AF13") (pinfunction "DIFFIO_RX_B22n_AF13") (pintype "bidirectional"))
    )
    (net (code "128") (name "/MIPI_CSI_DB3_HS_N") (class "Default")
      (node (ref "D2") (pin "AE14") (pinfunction "DIFFIO_RX_B23n_AE14") (pintype "bidirectional"))
    )
    (net (code "129") (name "/MIPI_CSI_DB3_HS_P") (class "Default")
      (node (ref "D2") (pin "AD14") (pinfunction "DIFFIO_RX_B23p_AD14") (pintype "bidirectional"))
    )
    (net (code "130") (name "/OSC_50_1") (class "Default")
      (node (ref "C9") (pin "1") (pinfunction "+_1") (pintype "passive"))
    )
    (net (code "131") (name "/OSC_50_2") (class "Default")
      (node (ref "C10") (pin "1") (pinfunction "+_1") (pintype "passive"))
    )
    (net (code "132") (name "/OSC_50_B3B") (class "Default")
      (node (ref "C9") (pin "2") (pinfunction "-_2") (pintype "passive"))
      (node (ref "D2") (pin "AF14") (pinfunction "CLK0p_AF14") (pintype "bidirectional"))
      (node (ref "R43") (pin "1") (pinfunction "+_1") (pintype "passive"))
      (node (ref "R44") (pin "1") (pinfunction "+_1") (pintype "passive"))
    )
    (net (code "137") (name "/OSC_50_B4B") (class "Default")
      (node (ref "C10") (pin "2") (pinfunction "-_2") (pintype "passive"))
      (node (ref "D2") (pin "AA16") (pinfunction "CLK2p_AA16") (pintype "bidirectional"))
      (node (ref "R45") (pin "1") (pinfunction "+_1") (pintype "passive"))
      (node (ref "R46") (pin "1") (pinfunction "+_1") (pintype "passive"))
    )
    (net (code "138") (name "DDR3_VREF_FPGA") (class "Default")
      (node (ref "C15") (pin "1") (pinfunction "+_1") (pintype "passive"))
      (node (ref "D5") (pin "6") (pinfunction "REFOUT_6") (pintype "power_in"))
      (node (ref "U1") (pin "H1") (pinfunction "VREFDQ_H1") (pintype "input"))
      (node (ref "U1") (pin "M8") (pinfunction "VREFCA_M8") (pintype "input"))
      (node (ref "U2") (pin "H1") (pinfunction "VREFDQ_H1") (pintype "input"))
      (node (ref "U2") (pin "M8") (pinfunction "VREFCA_M8") (pintype "input"))
    )
    (net (code "139") (name "DDR3_VTT_FPGA") (class "Default")
      (node (ref "C17") (pin "1") (pinfunction "+_1") (pintype "passive"))
      (node (ref "C18") (pin "1") (pinfunction "+_1") (pintype "passive"))
      (node (ref "C6") (pin "5") (pintype "passive"))
      (node (ref "C6") (pin "6") (pintype "passive"))
      (node (ref "C6") (pin "7") (pintype "passive"))
      (node (ref "C6") (pin "8") (pintype "passive"))
      (node (ref "C7") (pin "5") (pintype "passive"))
      (node (ref "C7") (pin "6") (pintype "passive"))
      (node (ref "C7") (pin "7") (pintype "passive"))
      (node (ref "C7") (pin "8") (pintype "passive"))
      (node (ref "C8") (pin "5") (pintype "passive"))
      (node (ref "C8") (pin "6") (pintype "passive"))
      (node (ref "C8") (pin "7") (pintype "passive"))
      (node (ref "C8") (pin "8") (pintype "passive"))
      (node (ref "D5") (pin "3") (pinfunction "VO_3") (pintype "power_in"))
      (node (ref "D5") (pin "5") (pinfunction "VOSNS_5") (pintype "input"))
      (node (ref "R40") (pin "10") (pintype "passive"))
      (node (ref "R40") (pin "11") (pintype "passive"))
      (node (ref "R40") (pin "12") (pintype "passive"))
      (node (ref "R40") (pin "13") (pintype "passive"))
      (node (ref "R40") (pin "14") (pintype "passive"))
      (node (ref "R40") (pin "15") (pintype "passive"))
      (node (ref "R40") (pin "16") (pintype "passive"))
      (node (ref "R40") (pin "9") (pintype "passive"))
      (node (ref "R41") (pin "10") (pintype "passive"))
      (node (ref "R41") (pin "11") (pintype "passive"))
      (node (ref "R41") (pin "12") (pintype "passive"))
      (node (ref "R41") (pin "13") (pintype "passive"))
      (node (ref "R41") (pin "14") (pintype "passive"))
      (node (ref "R41") (pin "15") (pintype "passive"))
      (node (ref "R41") (pin "16") (pintype "passive"))
      (node (ref "R41") (pin "9") (pintype "passive"))
      (node (ref "R42") (pin "10") (pintype "passive"))
      (node (ref "R42") (pin "11") (pintype "passive"))
      (node (ref "R42") (pin "12") (pintype "passive"))
      (node (ref "R42") (pin "13") (pintype "passive"))
      (node (ref "R42") (pin "14") (pintype "passive"))
      (node (ref "R42") (pin "15") (pintype "passive"))
      (node (ref "R42") (pin "16") (pintype "passive"))
      (node (ref "R42") (pin "9") (pintype "passive"))
    )
    (net (code "140") (name "GND") (class "Default")
      (node (ref "C11") (pin "2") (pinfunction "-_2") (pintype "passive"))
      (node (ref "C12") (pin "2") (pinfunction "-_2") (pintype "passive"))
      (node (ref "C13") (pin "2") (pinfunction "-_2") (pintype "passive"))
      (node (ref "C14") (pin "2") (pinfunction "-_2") (pintype "passive"))
      (node (ref "C15") (pin "2") (pinfunction "-_2") (pintype "passive"))
      (node (ref "C16") (pin "2") (pinfunction "-_2") (pintype "passive"))
      (node (ref "C17") (pin "2") (pinfunction "-_2") (pintype "passive"))
      (node (ref "C18") (pin "2") (pinfunction "-_2") (pintype "passive"))
      (node (ref "C19") (pin "2") (pinfunction "-_2") (pintype "passive"))
      (node (ref "C20") (pin "2") (pinfunction "-_2") (pintype "passive"))
      (node (ref "C6") (pin "1") (pintype "passive"))
      (node (ref "C6") (pin "2") (pintype "passive"))
      (node (ref "C6") (pin "3") (pintype "passive"))
      (node (ref "C6") (pin "4") (pintype "passive"))
      (node (ref "C7") (pin "1") (pintype "passive"))
      (node (ref "C7") (pin "2") (pintype "passive"))
      (node (ref "C7") (pin "3") (pintype "passive"))
      (node (ref "C7") (pin "4") (pintype "passive"))
      (node (ref "C8") (pin "1") (pintype "passive"))
      (node (ref "C8") (pin "2") (pintype "passive"))
      (node (ref "C8") (pin "3") (pintype "passive"))
      (node (ref "C8") (pin "4") (pintype "passive"))
      (node (ref "D2") (pin "AF15") (pinfunction "CLK0n_AF15") (pintype "bidirectional"))
      (node (ref "D2") (pin "AJ10") (pinfunction "GND_AJ10") (pintype "bidirectional"))
      (node (ref "D2") (pin "AJ22") (pinfunction "GND_AJ22") (pintype "bidirectional"))
      (node (ref "D2") (pin "AJ7") (pinfunction "GND_AJ7") (pintype "bidirectional"))
      (node (ref "D3") (pin "11") (pinfunction "GND_11") (pintype "power_in"))
      (node (ref "D4") (pin "11") (pinfunction "GND_11") (pintype "power_in"))
      (node (ref "D5") (pin "11") (pinfunction "EP_11") (pintype "power_in"))
      (node (ref "D5") (pin "4") (pinfunction "PGND_4") (pintype "power_in"))
      (node (ref "D5") (pin "8") (pinfunction "GND_8") (pintype "power_in"))
      (node (ref "R190") (pin "1") (pinfunction "+_1") (pintype "passive"))
      (node (ref "R44") (pin "2") (pinfunction "-_2") (pintype "passive"))
      (node (ref "R46") (pin "2") (pinfunction "-_2") (pintype "passive"))
      (node (ref "R47") (pin "2") (pinfunction "-_2") (pintype "passive"))
      (node (ref "R48") (pin "2") (pinfunction "-_2") (pintype "passive"))
      (node (ref "R57") (pin "2") (pinfunction "-_2") (pintype "passive"))
      (node (ref "R59") (pin "1") (pinfunction "+_1") (pintype "passive"))
      (node (ref "U1") (pin "A9") (pinfunction "VSS_A9") (pintype "power_in"))
      (node (ref "U1") (pin "B1") (pinfunction "VSSQ_B1") (pintype "power_in"))
      (node (ref "U1") (pin "B3") (pinfunction "VSS_B3") (pintype "power_in"))
      (node (ref "U1") (pin "B9") (pinfunction "VSSQ_B9") (pintype "power_in"))
      (node (ref "U1") (pin "D1") (pinfunction "VSSQ_D1") (pintype "power_in"))
      (node (ref "U1") (pin "D8") (pinfunction "VSSQ_D8") (pintype "power_in"))
      (node (ref "U1") (pin "E1") (pinfunction "VSS_E1") (pintype "power_in"))
      (node (ref "U1") (pin "E2") (pinfunction "VSSQ_E2") (pintype "power_in"))
      (node (ref "U1") (pin "E8") (pinfunction "VSSQ_E8") (pintype "power_in"))
      (node (ref "U1") (pin "F9") (pinfunction "VSSQ_F9") (pintype "power_in"))
      (node (ref "U1") (pin "G1") (pinfunction "VSSQ_G1") (pintype "power_in"))
      (node (ref "U1") (pin "G8") (pinfunction "VSS_G8") (pintype "power_in"))
      (node (ref "U1") (pin "G9") (pinfunction "VSSQ_G9") (pintype "power_in"))
      (node (ref "U1") (pin "J2") (pinfunction "VSS_J2") (pintype "power_in"))
      (node (ref "U1") (pin "J8") (pinfunction "VSS_J8") (pintype "power_in"))
      (node (ref "U1") (pin "M1") (pinfunction "VSS_M1") (pintype "power_in"))
      (node (ref "U1") (pin "M9") (pinfunction "VSS_M9") (pintype "power_in"))
      (node (ref "U1") (pin "P1") (pinfunction "VSS_P1") (pintype "power_in"))
      (node (ref "U1") (pin "P9") (pinfunction "VSS_P9") (pintype "power_in"))
      (node (ref "U1") (pin "T1") (pinfunction "VSS_T1") (pintype "power_in"))
      (node (ref "U1") (pin "T9") (pinfunction "VSS_T9") (pintype "power_in"))
      (node (ref "U2") (pin "A9") (pinfunction "VSS_A9") (pintype "power_in"))
      (node (ref "U2") (pin "B1") (pinfunction "VSSQ_B1") (pintype "power_in"))
      (node (ref "U2") (pin "B3") (pinfunction "VSS_B3") (pintype "power_in"))
      (node (ref "U2") (pin "B9") (pinfunction "VSSQ_B9") (pintype "power_in"))
      (node (ref "U2") (pin "D1") (pinfunction "VSSQ_D1") (pintype "power_in"))
      (node (ref "U2") (pin "D8") (pinfunction "VSSQ_D8") (pintype "power_in"))
      (node (ref "U2") (pin "E1") (pinfunction "VSS_E1") (pintype "power_in"))
      (node (ref "U2") (pin "E2") (pinfunction "VSSQ_E2") (pintype "power_in"))
      (node (ref "U2") (pin "E8") (pinfunction "VSSQ_E8") (pintype "power_in"))
      (node (ref "U2") (pin "F9") (pinfunction "VSSQ_F9") (pintype "power_in"))
      (node (ref "U2") (pin "G1") (pinfunction "VSSQ_G1") (pintype "power_in"))
      (node (ref "U2") (pin "G8") (pinfunction "VSS_G8") (pintype "power_in"))
      (node (ref "U2") (pin "G9") (pinfunction "VSSQ_G9") (pintype "power_in"))
      (node (ref "U2") (pin "J2") (pinfunction "VSS_J2") (pintype "power_in"))
      (node (ref "U2") (pin "J8") (pinfunction "VSS_J8") (pintype "power_in"))
      (node (ref "U2") (pin "M1") (pinfunction "VSS_M1") (pintype "power_in"))
      (node (ref "U2") (pin "M9") (pinfunction "VSS_M9") (pintype "power_in"))
      (node (ref "U2") (pin "P1") (pinfunction "VSS_P1") (pintype "power_in"))
      (node (ref "U2") (pin "P9") (pinfunction "VSS_P9") (pintype "power_in"))
      (node (ref "U2") (pin "T1") (pinfunction "VSS_T1") (pintype "power_in"))
      (node (ref "U2") (pin "T9") (pinfunction "VSS_T9") (pintype "power_in"))
    )
    (net (code "141") (name "Net-(C20-+)") (class "Default")
      (node (ref "C20") (pin "1") (pinfunction "+_1") (pintype "passive"))
      (node (ref "D5") (pin "1") (pinfunction "REFIN_1") (pintype "input"))
      (node (ref "R58") (pin "2") (pinfunction "-_2") (pintype "passive"))
      (node (ref "R59") (pin "2") (pinfunction "-_2") (pintype "passive"))
    )
    (net (code "142") (name "Net-(D2C-RZQ_0)") (class "Default")
      (node (ref "D2") (pin "AG17") (pinfunction "RZQ_0_AG17") (pintype "bidirectional"))
      (node (ref "R57") (pin "1") (pinfunction "+_1") (pintype "passive"))
    )
    (net (code "143") (name "Net-(D5-EN)") (class "Default")
      (node (ref "D5") (pin "7") (pinfunction "EN_7") (pintype "input"))
      (node (ref "R56") (pin "2") (pinfunction "-_2") (pintype "passive"))
    )
    (net (code "144") (name "Net-(D5-PGOOD)") (class "Default")
      (node (ref "D5") (pin "9") (pinfunction "PGOOD_9") (pintype "open_collector"))
      (node (ref "R55") (pin "2") (pinfunction "-_2") (pintype "passive"))
    )
    (net (code "145") (name "Net-(HL1-A)") (class "Default")
      (node (ref "HL1") (pin "1") (pinfunction "A_1") (pintype "passive"))
      (node (ref "R50") (pin "1") (pinfunction "+_1") (pintype "passive"))
    )
    (net (code "146") (name "Net-(HL2-A)") (class "Default")
      (node (ref "HL2") (pin "1") (pinfunction "A_1") (pintype "passive"))
      (node (ref "R52") (pin "1") (pinfunction "+_1") (pintype "passive"))
    )
    (net (code "147") (name "Net-(HL3-A)") (class "Default")
      (node (ref "HL3") (pin "1") (pinfunction "A_1") (pintype "passive"))
      (node (ref "R54") (pin "1") (pinfunction "+_1") (pintype "passive"))
    )
    (net (code "148") (name "Net-(R47-+)") (class "Default")
      (node (ref "R47") (pin "1") (pinfunction "+_1") (pintype "passive"))
      (node (ref "U1") (pin "L8") (pinfunction "ZQ_L8") (pintype "input"))
    )
    (net (code "149") (name "Net-(R48-+)") (class "Default")
      (node (ref "R48") (pin "1") (pinfunction "+_1") (pintype "passive"))
      (node (ref "U2") (pin "L8") (pinfunction "ZQ_L8") (pintype "input"))
    )
    (net (code "150") (name "VCC1P8") (class "Default")
      (node (ref "R43") (pin "2") (pinfunction "-_2") (pintype "passive"))
      (node (ref "R45") (pin "2") (pinfunction "-_2") (pintype "passive"))
    )
    (net (code "151") (name "VCC1P35_DDR3") (class "Default")
      (node (ref "C11") (pin "1") (pinfunction "+_1") (pintype "passive"))
      (node (ref "C13") (pin "1") (pinfunction "+_1") (pintype "passive"))
      (node (ref "C19") (pin "1") (pinfunction "+_1") (pintype "passive"))
      (node (ref "D3") (pin "2") (pinfunction "VCCA_2") (pintype "power_in"))
      (node (ref "D4") (pin "2") (pinfunction "VCCA_2") (pintype "power_in"))
      (node (ref "D5") (pin "2") (pinfunction "VLDOIN_2") (pintype "power_in"))
      (node (ref "R49") (pin "1") (pinfunction "+_1") (pintype "passive"))
      (node (ref "R58") (pin "1") (pinfunction "+_1") (pintype "passive"))
      (node (ref "U1") (pin "A1") (pinfunction "VDDQ_A1") (pintype "power_in"))
      (node (ref "U1") (pin "A8") (pinfunction "VDDQ_A8") (pintype "power_in"))
      (node (ref "U1") (pin "B2") (pinfunction "VDD_B2") (pintype "power_in"))
      (node (ref "U1") (pin "C1") (pinfunction "VDDQ_C1") (pintype "power_in"))
      (node (ref "U1") (pin "C9") (pinfunction "VDDQ_C9") (pintype "power_in"))
      (node (ref "U1") (pin "D2") (pinfunction "VDDQ_D2") (pintype "power_in"))
      (node (ref "U1") (pin "D9") (pinfunction "VDD_D9") (pintype "power_in"))
      (node (ref "U1") (pin "E9") (pinfunction "VDDQ_E9") (pintype "power_in"))
      (node (ref "U1") (pin "F1") (pinfunction "VDDQ_F1") (pintype "power_in"))
      (node (ref "U1") (pin "G7") (pinfunction "VDD_G7") (pintype "power_in"))
      (node (ref "U1") (pin "H2") (pinfunction "VDDQ_H2") (pintype "power_in"))
      (node (ref "U1") (pin "H9") (pinfunction "VDDQ_H9") (pintype "power_in"))
      (node (ref "U1") (pin "K2") (pinfunction "VDD_K2") (pintype "power_in"))
      (node (ref "U1") (pin "K8") (pinfunction "VDD_K8") (pintype "power_in"))
      (node (ref "U1") (pin "N1") (pinfunction "VDD_N1") (pintype "power_in"))
      (node (ref "U1") (pin "N9") (pinfunction "VDD_N9") (pintype "power_in"))
      (node (ref "U1") (pin "R1") (pinfunction "VDD_R1") (pintype "power_in"))
      (node (ref "U1") (pin "R9") (pinfunction "VDD_R9") (pintype "power_in"))
      (node (ref "U2") (pin "A1") (pinfunction "VDDQ_A1") (pintype "power_in"))
      (node (ref "U2") (pin "A8") (pinfunction "VDDQ_A8") (pintype "power_in"))
      (node (ref "U2") (pin "B2") (pinfunction "VDD_B2") (pintype "power_in"))
      (node (ref "U2") (pin "C1") (pinfunction "VDDQ_C1") (pintype "power_in"))
      (node (ref "U2") (pin "C9") (pinfunction "VDDQ_C9") (pintype "power_in"))
      (node (ref "U2") (pin "D2") (pinfunction "VDDQ_D2") (pintype "power_in"))
      (node (ref "U2") (pin "D9") (pinfunction "VDD_D9") (pintype "power_in"))
      (node (ref "U2") (pin "E9") (pinfunction "VDDQ_E9") (pintype "power_in"))
      (node (ref "U2") (pin "F1") (pinfunction "VDDQ_F1") (pintype "power_in"))
      (node (ref "U2") (pin "G7") (pinfunction "VDD_G7") (pintype "power_in"))
      (node (ref "U2") (pin "H2") (pinfunction "VDDQ_H2") (pintype "power_in"))
      (node (ref "U2") (pin "H9") (pinfunction "VDDQ_H9") (pintype "power_in"))
      (node (ref "U2") (pin "K2") (pinfunction "VDD_K2") (pintype "power_in"))
      (node (ref "U2") (pin "K8") (pinfunction "VDD_K8") (pintype "power_in"))
      (node (ref "U2") (pin "N1") (pinfunction "VDD_N1") (pintype "power_in"))
      (node (ref "U2") (pin "N9") (pinfunction "VDD_N9") (pintype "power_in"))
      (node (ref "U2") (pin "R1") (pinfunction "VDD_R1") (pintype "power_in"))
      (node (ref "U2") (pin "R9") (pinfunction "VDD_R9") (pintype "power_in"))
    )
    (net (code "152") (name "VCC2P5") (class "Default")
      (node (ref "R50") (pin "2") (pinfunction "-_2") (pintype "passive"))
      (node (ref "R52") (pin "2") (pinfunction "-_2") (pintype "passive"))
      (node (ref "R54") (pin "2") (pinfunction "-_2") (pintype "passive"))
    )
    (net (code "153") (name "VCC3P3") (class "Default")
      (node (ref "C12") (pin "1") (pinfunction "+_1") (pintype "passive"))
      (node (ref "C14") (pin "1") (pinfunction "+_1") (pintype "passive"))
      (node (ref "C16") (pin "1") (pinfunction "+_1") (pintype "passive"))
      (node (ref "D3") (pin "19") (pinfunction "VCCB_19") (pintype "power_in"))
      (node (ref "D4") (pin "19") (pinfunction "VCCB_19") (pintype "power_in"))
      (node (ref "D5") (pin "10") (pinfunction "VIN_10") (pintype "power_in"))
      (node (ref "R55") (pin "1") (pinfunction "+_1") (pintype "passive"))
      (node (ref "R56") (pin "1") (pinfunction "+_1") (pintype "passive"))
    )
    (net (code "154") (name "unconnected-(D2B-DIFFIO_RX_B22p-PadAE13)") (class "Default")
      (node (ref "D2") (pin "AE13") (pinfunction "DIFFIO_RX_B22p_AE13") (pintype "bidirectional"))
    )
    (net (code "155") (name "unconnected-(D2C-CLK2n-PadAB17)") (class "Default")
      (node (ref "D2") (pin "AB17") (pinfunction "CLK2n_AB17") (pintype "bidirectional"))
    )
    (net (code "156") (name "unconnected-(D2C-CLK3n-PadAD17)") (class "Default")
      (node (ref "D2") (pin "AD17") (pinfunction "CLK3n_AD17") (pintype "bidirectional"))
    )
    (net (code "157") (name "unconnected-(D2C-CLK3p-PadAC18)") (class "Default")
      (node (ref "D2") (pin "AC18") (pinfunction "CLK3p_AC18") (pintype "bidirectional"))
    )
    (net (code "158") (name "unconnected-(D2C-GND-PadAA19)") (class "Default")
      (node (ref "D2") (pin "AA19") (pinfunction "GND_AA19") (pintype "bidirectional"))
    )
    (net (code "159") (name "unconnected-(D2C-GND-PadAA21)") (class "Default")
      (node (ref "D2") (pin "AA21") (pinfunction "GND_AA21") (pintype "bidirectional"))
    )
    (net (code "160") (name "unconnected-(D2C-GND-PadAB21)") (class "Default")
      (node (ref "D2") (pin "AB21") (pinfunction "GND_AB21") (pintype "bidirectional"))
    )
    (net (code "161") (name "unconnected-(D2C-GND-PadAF26)") (class "Default")
      (node (ref "D2") (pin "AF26") (pinfunction "GND_AF26") (pintype "bidirectional"))
    )
    (net (code "162") (name "unconnected-(D2C-GND-PadAG26)") (class "Default")
      (node (ref "D2") (pin "AG26") (pinfunction "GND_AG26") (pintype "bidirectional"))
    )
    (net (code "163") (name "unconnected-(D2C-GND-PadAH19)") (class "Default")
      (node (ref "D2") (pin "AH19") (pinfunction "GND_AH19") (pintype "bidirectional"))
    )
    (net (code "164") (name "unconnected-(D2C-GND-PadAH22)") (class "Default")
      (node (ref "D2") (pin "AH22") (pinfunction "GND_AH22") (pintype "bidirectional"))
    )
    (net (code "165") (name "unconnected-(D2C-GND-PadAH25)") (class "Default")
      (node (ref "D2") (pin "AH25") (pinfunction "GND_AH25") (pintype "bidirectional"))
    )
    (net (code "166") (name "unconnected-(D2C-GND-PadAJ25)") (class "Default")
      (node (ref "D2") (pin "AJ25") (pinfunction "GND_AJ25") (pintype "bidirectional"))
    )
    (net (code "167") (name "unconnected-(D2C-GND-PadAJ26)") (class "Default")
      (node (ref "D2") (pin "AJ26") (pinfunction "GND_AJ26") (pintype "bidirectional"))
    )
    (net (code "168") (name "unconnected-(D2C-GND-PadAK29)") (class "Default")
      (node (ref "D2") (pin "AK29") (pinfunction "GND_AK29") (pintype "bidirectional"))
    )
    (net (code "169") (name "unconnected-(D2C-GND-PadV18)") (class "Default")
      (node (ref "D2") (pin "V18") (pinfunction "GND_V18") (pintype "bidirectional"))
    )
    (net (code "170") (name "unconnected-(D2C-GND-PadW19)") (class "Default")
      (node (ref "D2") (pin "W19") (pinfunction "GND_W19") (pintype "bidirectional"))
    )
    (net (code "171") (name "unconnected-(D2C-GND-PadY18)") (class "Default")
      (node (ref "D2") (pin "Y18") (pinfunction "GND_Y18") (pintype "bidirectional"))
    )
    (net (code "172") (name "unconnected-(U1C-NC-PadJ1)") (class "Default")
      (node (ref "U1") (pin "J1") (pinfunction "NC_J1") (pintype "passive"))
    )
    (net (code "173") (name "unconnected-(U1C-NC-PadJ9)") (class "Default")
      (node (ref "U1") (pin "J9") (pinfunction "NC_J9") (pintype "passive"))
    )
    (net (code "174") (name "unconnected-(U1C-NC-PadL1)") (class "Default")
      (node (ref "U1") (pin "L1") (pinfunction "NC_L1") (pintype "passive"))
    )
    (net (code "175") (name "unconnected-(U1C-NC-PadL9)") (class "Default")
      (node (ref "U1") (pin "L9") (pinfunction "NC_L9") (pintype "passive"))
    )
    (net (code "176") (name "unconnected-(U1C-NC-PadM7)") (class "Default")
      (node (ref "U1") (pin "M7") (pinfunction "NC_M7") (pintype "passive"))
    )
    (net (code "177") (name "unconnected-(U2C-NC-PadJ1)") (class "Default")
      (node (ref "U2") (pin "J1") (pinfunction "NC_J1") (pintype "passive"))
    )
    (net (code "178") (name "unconnected-(U2C-NC-PadJ9)") (class "Default")
      (node (ref "U2") (pin "J9") (pinfunction "NC_J9") (pintype "passive"))
    )
    (net (code "179") (name "unconnected-(U2C-NC-PadL1)") (class "Default")
      (node (ref "U2") (pin "L1") (pinfunction "NC_L1") (pintype "passive"))
    )
    (net (code "180") (name "unconnected-(U2C-NC-PadL9)") (class "Default")
      (node (ref "U2") (pin "L9") (pinfunction "NC_L9") (pintype "passive"))
    )
    (net (code "181") (name "unconnected-(U2C-NC-PadM7)") (class "Default")
      (node (ref "U2") (pin "M7") (pinfunction "NC_M7") (pintype "passive"))
    )
  )
)
